# R111E.net
KiCad netlist of a schematic drawn in EAGLE
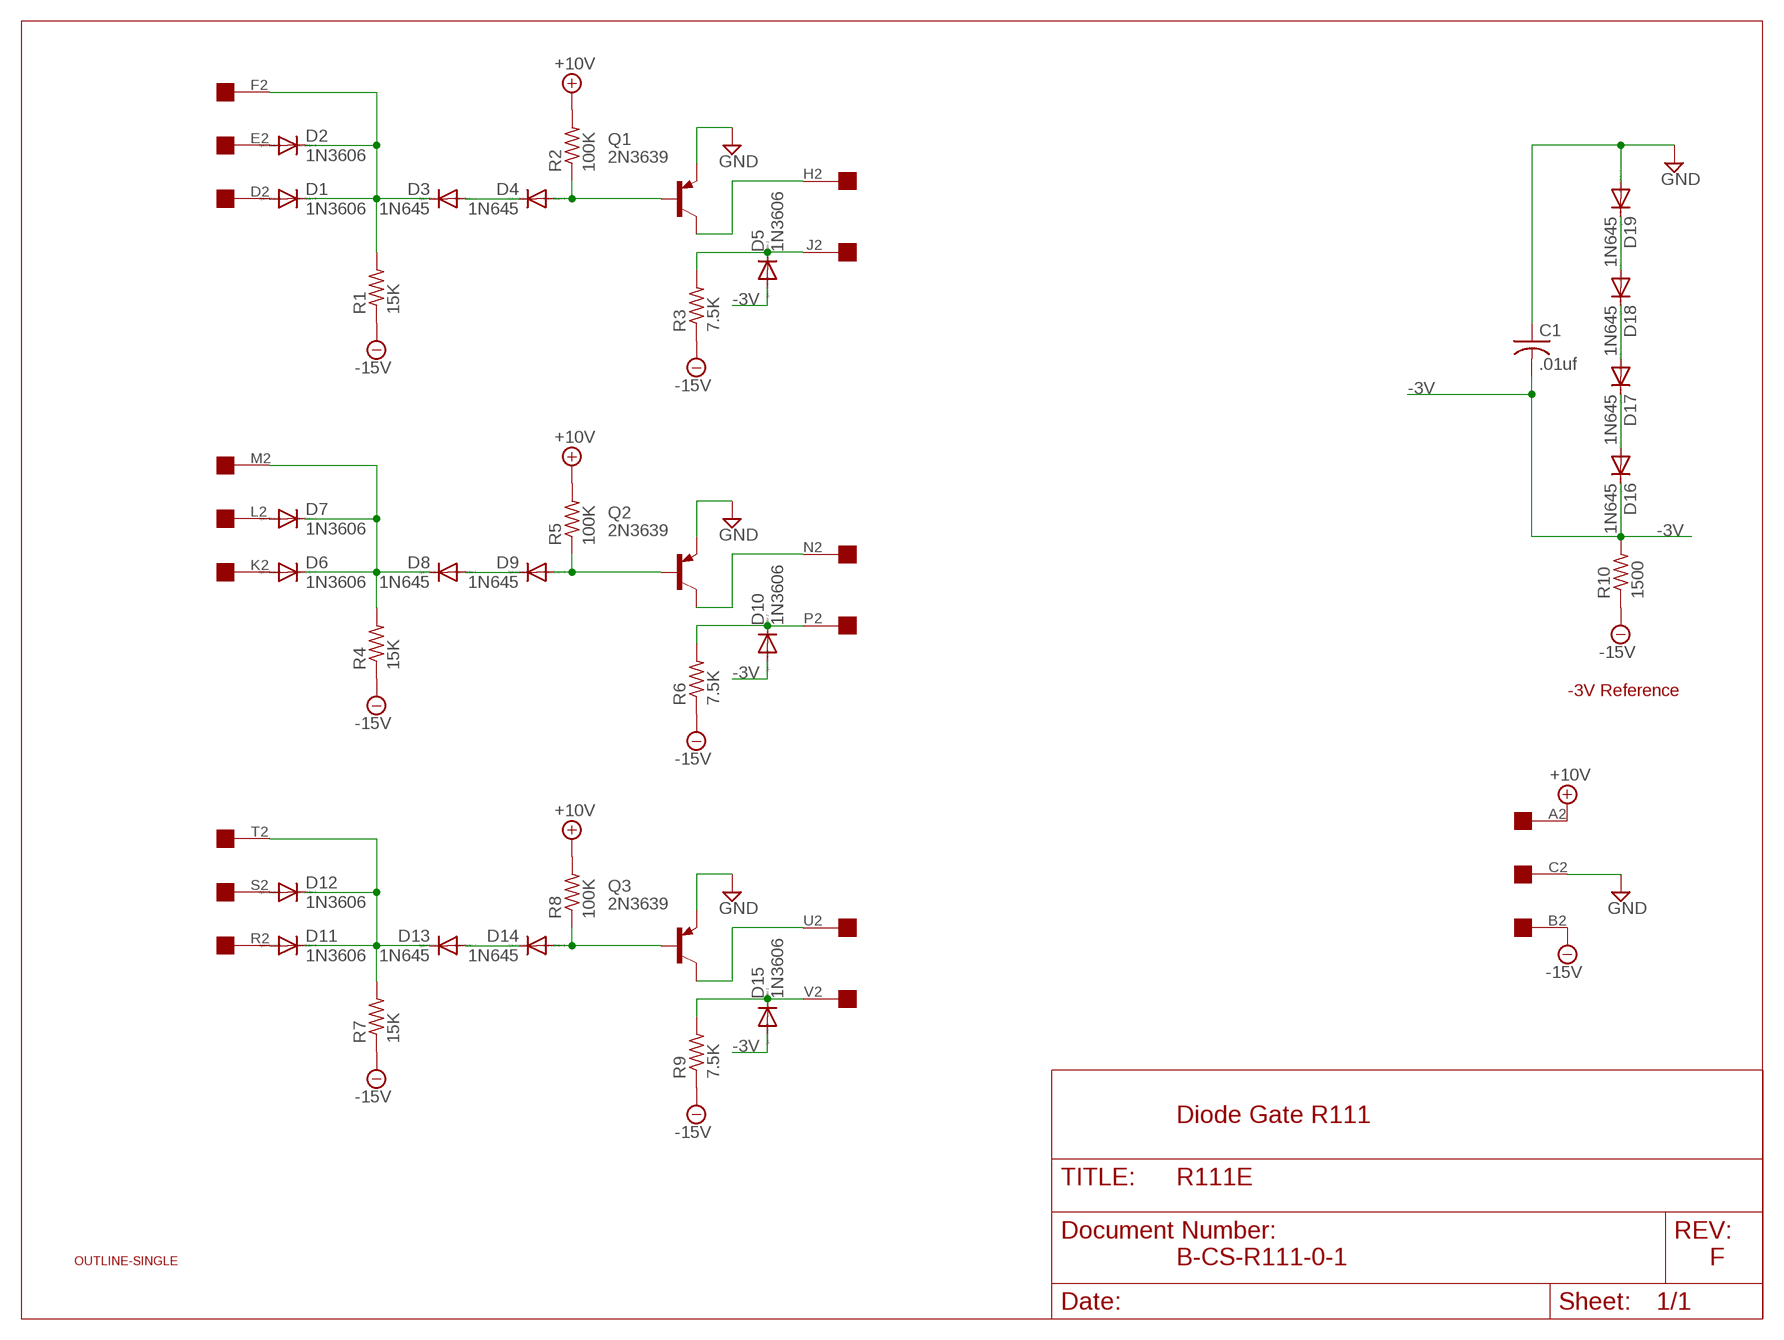
[diagram p0: schematic, sheet 1]

(export (version "E")
  (design (tool "Eeschema 10.0.6"))
  (components
    (comp (ref "C1")
      (value ".01uf")
      (footprint "eagle-import:C150-054X183")
      (libsource (lib "eagle-import") (part "C-US150-054X183"))
    )
    (comp (ref "D1")
      (value "1N3606")
      (footprint "eagle-import:DO35-10")
      (libsource (lib "eagle-import") (part "1N4148DO35-10"))
    )
    (comp (ref "D2")
      (value "1N3606")
      (footprint "eagle-import:DO35-10")
      (libsource (lib "eagle-import") (part "1N4148DO35-10"))
    )
    (comp (ref "D3")
      (value "1N645")
      (footprint "eagle-import:DO35-10")
      (libsource (lib "eagle-import") (part "1N4148DO35-10"))
    )
    (comp (ref "D4")
      (value "1N645")
      (footprint "eagle-import:DO35-10")
      (libsource (lib "eagle-import") (part "1N4148DO35-10"))
    )
    (comp (ref "D5")
      (value "1N3606")
      (footprint "eagle-import:DO35-10")
      (libsource (lib "eagle-import") (part "1N4148DO35-10"))
    )
    (comp (ref "D6")
      (value "1N3606")
      (footprint "eagle-import:DO35-10")
      (libsource (lib "eagle-import") (part "1N4148DO35-10"))
    )
    (comp (ref "D7")
      (value "1N3606")
      (footprint "eagle-import:DO35-10")
      (libsource (lib "eagle-import") (part "1N4148DO35-10"))
    )
    (comp (ref "D8")
      (value "1N645")
      (footprint "eagle-import:DO35-10")
      (libsource (lib "eagle-import") (part "1N4148DO35-10"))
    )
    (comp (ref "D9")
      (value "1N645")
      (footprint "eagle-import:DO35-10")
      (libsource (lib "eagle-import") (part "1N4148DO35-10"))
    )
    (comp (ref "D10")
      (value "1N3606")
      (footprint "eagle-import:DO35-10")
      (libsource (lib "eagle-import") (part "1N4148DO35-10"))
    )
    (comp (ref "D11")
      (value "1N3606")
      (footprint "eagle-import:DO35-10")
      (libsource (lib "eagle-import") (part "1N4148DO35-10"))
    )
    (comp (ref "D12")
      (value "1N3606")
      (footprint "eagle-import:DO35-10")
      (libsource (lib "eagle-import") (part "1N4148DO35-10"))
    )
    (comp (ref "D13")
      (value "1N645")
      (footprint "eagle-import:DO35-10")
      (libsource (lib "eagle-import") (part "1N4148DO35-10"))
    )
    (comp (ref "D14")
      (value "1N645")
      (footprint "eagle-import:DO35-10")
      (libsource (lib "eagle-import") (part "1N4148DO35-10"))
    )
    (comp (ref "D15")
      (value "1N3606")
      (footprint "eagle-import:DO35-10")
      (libsource (lib "eagle-import") (part "1N4148DO35-10"))
    )
    (comp (ref "D16")
      (value "1N645")
      (footprint "eagle-import:DO35-10")
      (libsource (lib "eagle-import") (part "1N4148DO35-10"))
    )
    (comp (ref "D17")
      (value "1N645")
      (footprint "eagle-import:DO35-10")
      (libsource (lib "eagle-import") (part "1N4148DO35-10"))
    )
    (comp (ref "D18")
      (value "1N645")
      (footprint "eagle-import:DO35-10")
      (libsource (lib "eagle-import") (part "1N4148DO35-10"))
    )
    (comp (ref "D19")
      (value "1N645")
      (footprint "eagle-import:DO35-10")
      (libsource (lib "eagle-import") (part "1N4148DO35-10"))
    )
    (comp (ref "Q1")
      (value "2N3639")
      (footprint "eagle-import:TO39")
      (libsource (lib "eagle-import") (part "2N3637"))
    )
    (comp (ref "Q2")
      (value "2N3639")
      (footprint "eagle-import:TO39")
      (libsource (lib "eagle-import") (part "2N3637"))
    )
    (comp (ref "Q3")
      (value "2N3639")
      (footprint "eagle-import:TO39")
      (libsource (lib "eagle-import") (part "2N3637"))
    )
    (comp (ref "R1")
      (value "15K")
      (footprint "eagle-import:0207_10")
      (libsource (lib "eagle-import") (part "R-US_0207/10"))
    )
    (comp (ref "R2")
      (value "100K")
      (footprint "eagle-import:0207_10")
      (libsource (lib "eagle-import") (part "R-US_0207/10"))
    )
    (comp (ref "R3")
      (value "7.5K")
      (footprint "eagle-import:0207_10")
      (libsource (lib "eagle-import") (part "R-US_0207/10"))
    )
    (comp (ref "R4")
      (value "15K")
      (footprint "eagle-import:0207_10")
      (libsource (lib "eagle-import") (part "R-US_0207/10"))
    )
    (comp (ref "R5")
      (value "100K")
      (footprint "eagle-import:0207_10")
      (libsource (lib "eagle-import") (part "R-US_0207/10"))
    )
    (comp (ref "R6")
      (value "7.5K")
      (footprint "eagle-import:0207_10")
      (libsource (lib "eagle-import") (part "R-US_0207/10"))
    )
    (comp (ref "R7")
      (value "15K")
      (footprint "eagle-import:0207_10")
      (libsource (lib "eagle-import") (part "R-US_0207/10"))
    )
    (comp (ref "R8")
      (value "100K")
      (footprint "eagle-import:0207_10")
      (libsource (lib "eagle-import") (part "R-US_0207/10"))
    )
    (comp (ref "R9")
      (value "7.5K")
      (footprint "eagle-import:0207_10")
      (libsource (lib "eagle-import") (part "R-US_0207/10"))
    )
    (comp (ref "R10")
      (value "1500")
      (footprint "eagle-import:0207_10")
      (libsource (lib "eagle-import") (part "R-US_0207/10"))
    )
    (comp (ref "U$1")
      (value "OUTLINE-SINGLE")
      (footprint "eagle-import:SINGLE")
      (libsource (lib "eagle-import") (part "OUTLINE-SINGLE"))
    )
    (comp (ref "U$2")
      (value "EDGE-1")
      (footprint "eagle-import:EDGE-CON1")
      (libsource (lib "eagle-import") (part "EDGE-1"))
    )
  )
  (nets
    (net (code "1") (name "+10V") (class "Default")
      (node (ref "R2") (pin "2") (pinfunction "2_2") (pintype "passive"))
      (node (ref "R5") (pin "2") (pinfunction "2_2") (pintype "passive"))
      (node (ref "R8") (pin "2") (pinfunction "2_2") (pintype "passive"))
      (node (ref "U$2") (pin "A2") (pinfunction "1_A2") (pintype "bidirectional"))
    )
    (net (code "2") (name "-15V") (class "Default")
      (node (ref "R1") (pin "1") (pinfunction "1_1") (pintype "passive"))
      (node (ref "R10") (pin "1") (pinfunction "1_1") (pintype "passive"))
      (node (ref "R3") (pin "1") (pinfunction "1_1") (pintype "passive"))
      (node (ref "R4") (pin "1") (pinfunction "1_1") (pintype "passive"))
      (node (ref "R6") (pin "1") (pinfunction "1_1") (pintype "passive"))
      (node (ref "R7") (pin "1") (pinfunction "1_1") (pintype "passive"))
      (node (ref "R9") (pin "1") (pinfunction "1_1") (pintype "passive"))
      (node (ref "U$2") (pin "B2") (pinfunction "1_B2") (pintype "bidirectional"))
    )
    (net (code "3") (name "/-3V") (class "Default")
      (node (ref "C1") (pin "2") (pinfunction "2_2") (pintype "passive"))
      (node (ref "D10") (pin "A") (pinfunction "A_A") (pintype "passive"))
      (node (ref "D15") (pin "A") (pinfunction "A_A") (pintype "passive"))
      (node (ref "D16") (pin "C") (pinfunction "C_C") (pintype "passive"))
      (node (ref "D5") (pin "A") (pinfunction "A_A") (pintype "passive"))
      (node (ref "R10") (pin "2") (pinfunction "2_2") (pintype "passive"))
    )
    (net (code "4") (name "GND") (class "Default")
      (node (ref "C1") (pin "1") (pinfunction "1_1") (pintype "passive"))
      (node (ref "D19") (pin "A") (pinfunction "A_A") (pintype "passive"))
      (node (ref "Q1") (pin "1") (pinfunction "E_1") (pintype "passive"))
      (node (ref "Q2") (pin "1") (pinfunction "E_1") (pintype "passive"))
      (node (ref "Q3") (pin "1") (pinfunction "E_1") (pintype "passive"))
      (node (ref "U$2") (pin "C2") (pinfunction "1_C2") (pintype "bidirectional"))
    )
    (net (code "5") (name "Net-(D3-PadA)") (class "Default")
      (node (ref "D3") (pin "A") (pinfunction "A_A") (pintype "passive"))
      (node (ref "D4") (pin "C") (pinfunction "C_C") (pintype "passive"))
    )
    (net (code "6") (name "Net-(D8-PadA)") (class "Default")
      (node (ref "D8") (pin "A") (pinfunction "A_A") (pintype "passive"))
      (node (ref "D9") (pin "C") (pinfunction "C_C") (pintype "passive"))
    )
    (net (code "7") (name "Net-(D13-PadA)") (class "Default")
      (node (ref "D13") (pin "A") (pinfunction "A_A") (pintype "passive"))
      (node (ref "D14") (pin "C") (pinfunction "C_C") (pintype "passive"))
    )
    (net (code "8") (name "Net-(D16-PadA)") (class "Default")
      (node (ref "D16") (pin "A") (pinfunction "A_A") (pintype "passive"))
      (node (ref "D17") (pin "C") (pinfunction "C_C") (pintype "passive"))
    )
    (net (code "9") (name "Net-(D17-PadA)") (class "Default")
      (node (ref "D17") (pin "A") (pinfunction "A_A") (pintype "passive"))
      (node (ref "D18") (pin "C") (pinfunction "C_C") (pintype "passive"))
    )
    (net (code "10") (name "Net-(D18-PadA)") (class "Default")
      (node (ref "D18") (pin "A") (pinfunction "A_A") (pintype "passive"))
      (node (ref "D19") (pin "C") (pinfunction "C_C") (pintype "passive"))
    )
    (net (code "11") (name "Net-(Q1-B)") (class "Default")
      (node (ref "D4") (pin "A") (pinfunction "A_A") (pintype "passive"))
      (node (ref "Q1") (pin "2") (pinfunction "B_2") (pintype "passive"))
      (node (ref "R2") (pin "1") (pinfunction "1_1") (pintype "passive"))
    )
    (net (code "12") (name "Net-(Q1-C)") (class "Default")
      (node (ref "Q1") (pin "3") (pinfunction "C_3") (pintype "passive"))
      (node (ref "U$2") (pin "H2") (pinfunction "1_H2") (pintype "bidirectional"))
    )
    (net (code "13") (name "Net-(Q2-B)") (class "Default")
      (node (ref "D9") (pin "A") (pinfunction "A_A") (pintype "passive"))
      (node (ref "Q2") (pin "2") (pinfunction "B_2") (pintype "passive"))
      (node (ref "R5") (pin "1") (pinfunction "1_1") (pintype "passive"))
    )
    (net (code "14") (name "Net-(Q2-C)") (class "Default")
      (node (ref "Q2") (pin "3") (pinfunction "C_3") (pintype "passive"))
      (node (ref "U$2") (pin "N2") (pinfunction "1_N2") (pintype "bidirectional"))
    )
    (net (code "15") (name "Net-(Q3-B)") (class "Default")
      (node (ref "D14") (pin "A") (pinfunction "A_A") (pintype "passive"))
      (node (ref "Q3") (pin "2") (pinfunction "B_2") (pintype "passive"))
      (node (ref "R8") (pin "1") (pinfunction "1_1") (pintype "passive"))
    )
    (net (code "16") (name "Net-(Q3-C)") (class "Default")
      (node (ref "Q3") (pin "3") (pinfunction "C_3") (pintype "passive"))
      (node (ref "U$2") (pin "U2") (pinfunction "1_U2") (pintype "bidirectional"))
    )
    (net (code "17") (name "Net-(U$2D-1)") (class "Default")
      (node (ref "D1") (pin "A") (pinfunction "A_A") (pintype "passive"))
      (node (ref "U$2") (pin "D2") (pinfunction "1_D2") (pintype "bidirectional"))
    )
    (net (code "18") (name "Net-(U$2E-1)") (class "Default")
      (node (ref "D2") (pin "A") (pinfunction "A_A") (pintype "passive"))
      (node (ref "U$2") (pin "E2") (pinfunction "1_E2") (pintype "bidirectional"))
    )
    (net (code "19") (name "Net-(U$2F-1)") (class "Default")
      (node (ref "D1") (pin "C") (pinfunction "C_C") (pintype "passive"))
      (node (ref "D2") (pin "C") (pinfunction "C_C") (pintype "passive"))
      (node (ref "D3") (pin "C") (pinfunction "C_C") (pintype "passive"))
      (node (ref "R1") (pin "2") (pinfunction "2_2") (pintype "passive"))
      (node (ref "U$2") (pin "F2") (pinfunction "1_F2") (pintype "bidirectional"))
    )
    (net (code "20") (name "Net-(U$2H-1)") (class "Default")
      (node (ref "D5") (pin "C") (pinfunction "C_C") (pintype "passive"))
      (node (ref "R3") (pin "2") (pinfunction "2_2") (pintype "passive"))
      (node (ref "U$2") (pin "J2") (pinfunction "1_J2") (pintype "bidirectional"))
    )
    (net (code "21") (name "Net-(U$2I-1)") (class "Default")
      (node (ref "D6") (pin "A") (pinfunction "A_A") (pintype "passive"))
      (node (ref "U$2") (pin "K2") (pinfunction "1_K2") (pintype "bidirectional"))
    )
    (net (code "22") (name "Net-(U$2J-1)") (class "Default")
      (node (ref "D7") (pin "A") (pinfunction "A_A") (pintype "passive"))
      (node (ref "U$2") (pin "L2") (pinfunction "1_L2") (pintype "bidirectional"))
    )
    (net (code "23") (name "Net-(U$2K-1)") (class "Default")
      (node (ref "D6") (pin "C") (pinfunction "C_C") (pintype "passive"))
      (node (ref "D7") (pin "C") (pinfunction "C_C") (pintype "passive"))
      (node (ref "D8") (pin "C") (pinfunction "C_C") (pintype "passive"))
      (node (ref "R4") (pin "2") (pinfunction "2_2") (pintype "passive"))
      (node (ref "U$2") (pin "M2") (pinfunction "1_M2") (pintype "bidirectional"))
    )
    (net (code "24") (name "Net-(U$2M-1)") (class "Default")
      (node (ref "D10") (pin "C") (pinfunction "C_C") (pintype "passive"))
      (node (ref "R6") (pin "2") (pinfunction "2_2") (pintype "passive"))
      (node (ref "U$2") (pin "P2") (pinfunction "1_P2") (pintype "bidirectional"))
    )
    (net (code "25") (name "Net-(U$2N-1)") (class "Default")
      (node (ref "D11") (pin "A") (pinfunction "A_A") (pintype "passive"))
      (node (ref "U$2") (pin "R2") (pinfunction "1_R2") (pintype "bidirectional"))
    )
    (net (code "26") (name "Net-(U$2O-1)") (class "Default")
      (node (ref "D12") (pin "A") (pinfunction "A_A") (pintype "passive"))
      (node (ref "U$2") (pin "S2") (pinfunction "1_S2") (pintype "bidirectional"))
    )
    (net (code "27") (name "Net-(U$2P-1)") (class "Default")
      (node (ref "D11") (pin "C") (pinfunction "C_C") (pintype "passive"))
      (node (ref "D12") (pin "C") (pinfunction "C_C") (pintype "passive"))
      (node (ref "D13") (pin "C") (pinfunction "C_C") (pintype "passive"))
      (node (ref "R7") (pin "2") (pinfunction "2_2") (pintype "passive"))
      (node (ref "U$2") (pin "T2") (pinfunction "1_T2") (pintype "bidirectional"))
    )
    (net (code "28") (name "Net-(U$2R-1)") (class "Default")
      (node (ref "D15") (pin "C") (pinfunction "C_C") (pintype "passive"))
      (node (ref "R9") (pin "2") (pinfunction "2_2") (pintype "passive"))
      (node (ref "U$2") (pin "V2") (pinfunction "1_V2") (pintype "bidirectional"))
    )
  )
)
